# USB3.net
KiCad netlist of a schematic drawn in Altium Designer
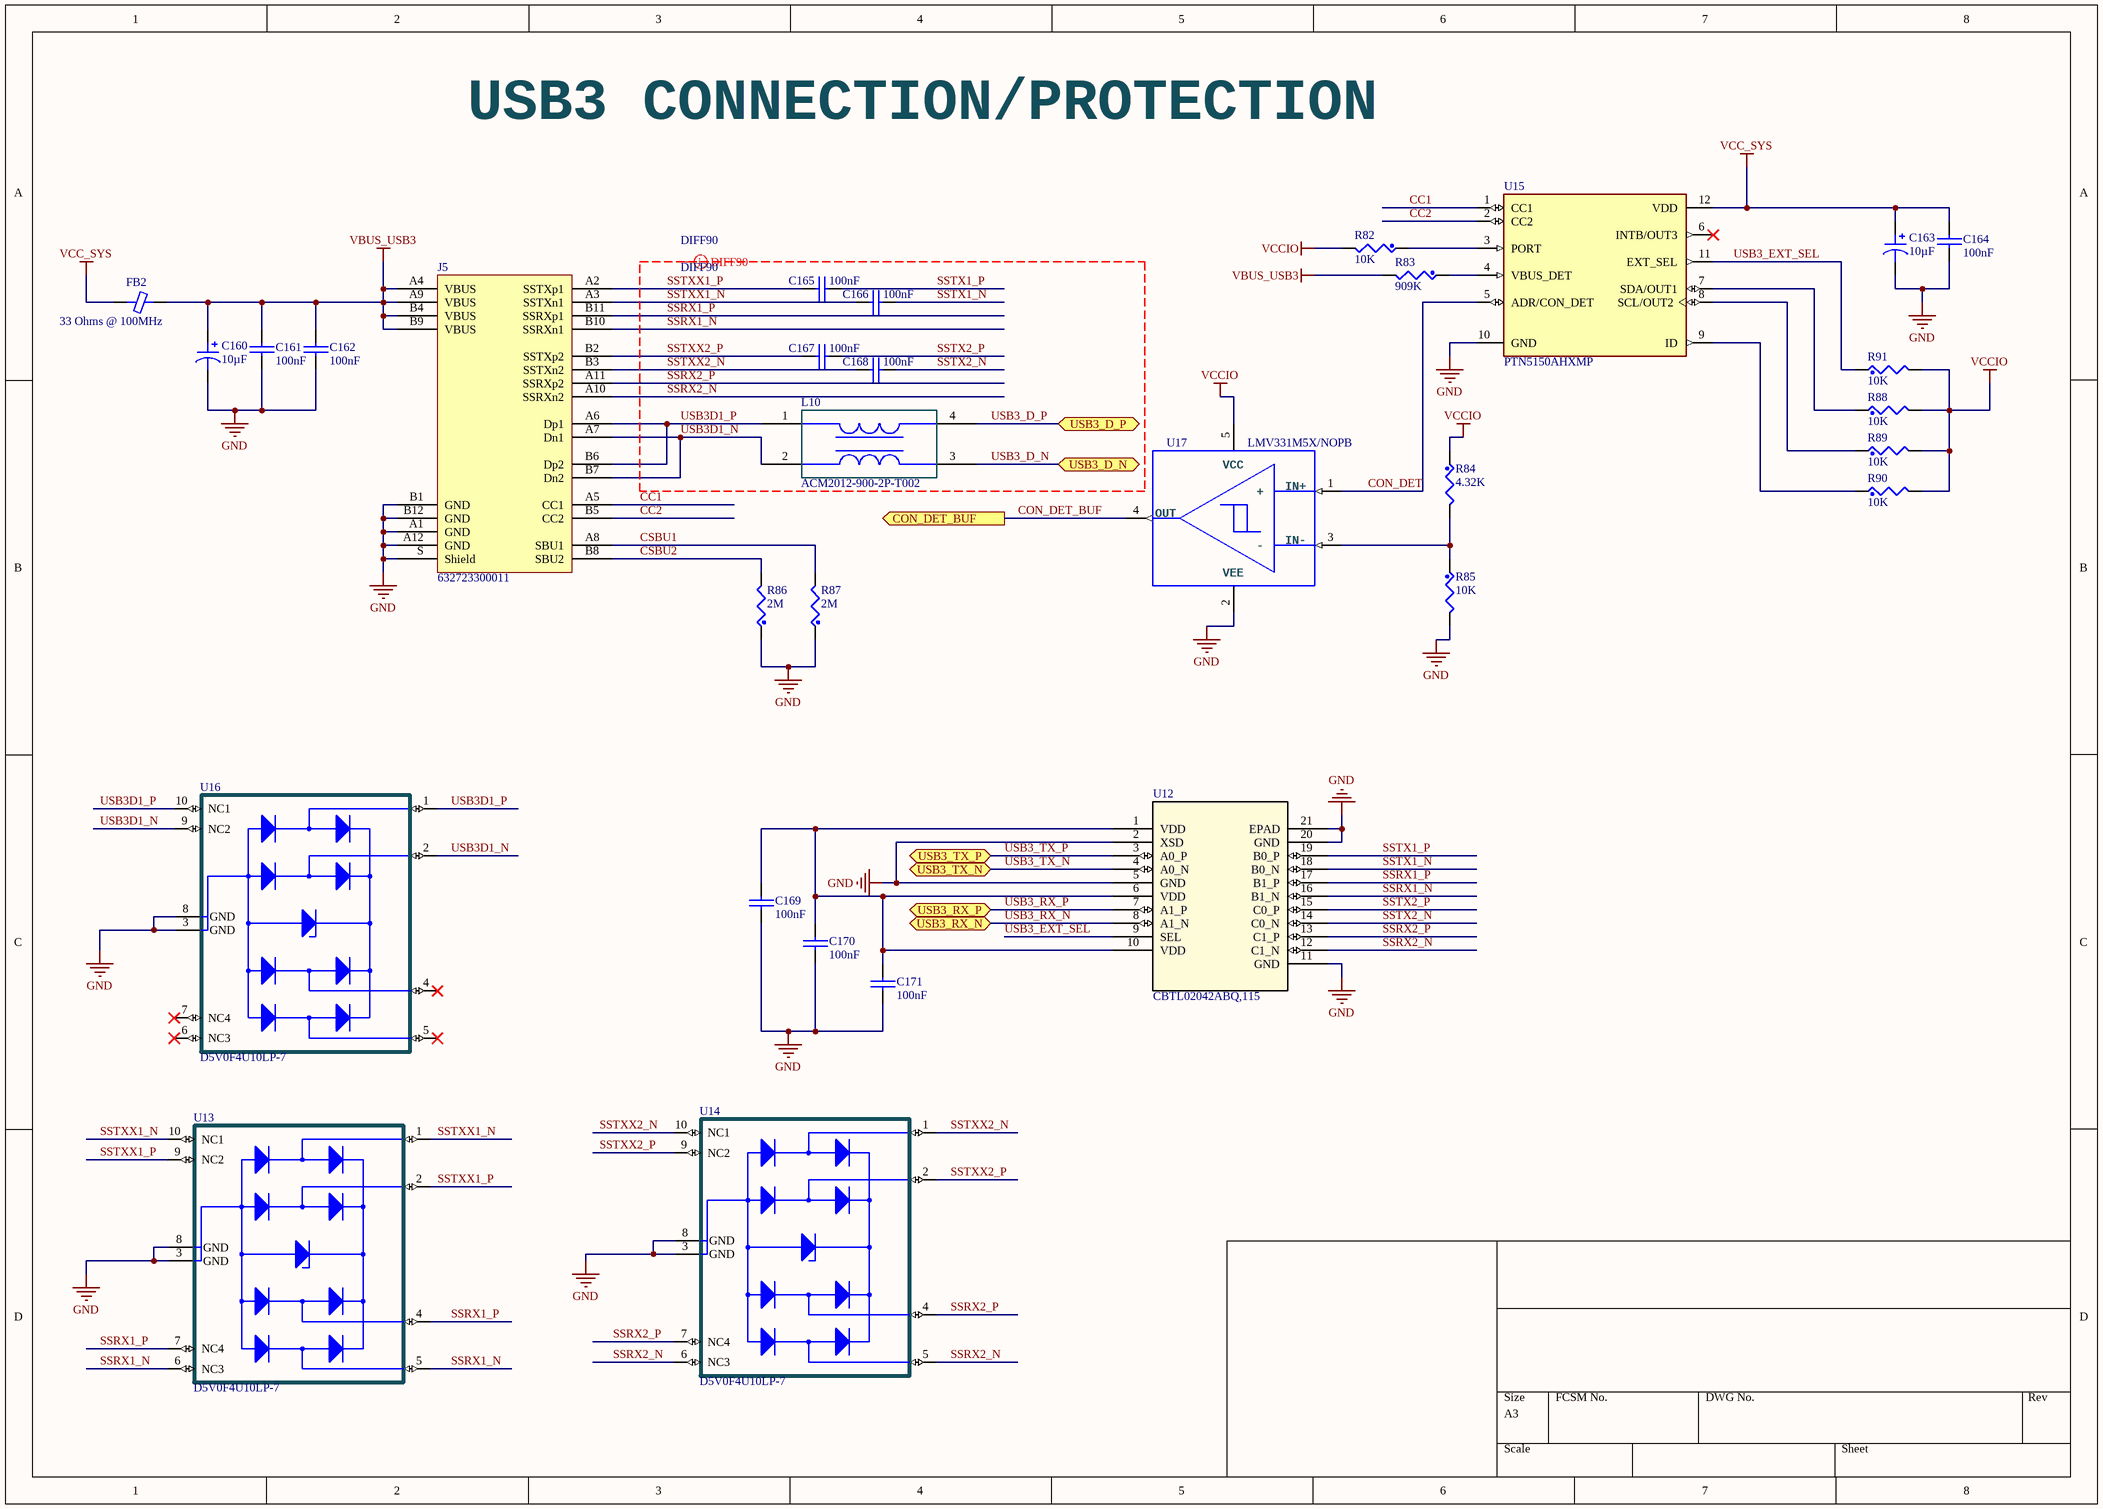
[diagram p0: USB3.SchDoc]

(export (version "E")
  (design (tool "Eeschema 10.0.6"))
  (components
    (comp (ref "C160")
      (value "10µF")
      (footprint "CAP POL 1206_3216")
      (description "CAP TANT 10UF 20% 10V 1206")
      (fields (field (name "PART NUMBER") "ATCC-211A-010-106M-T") (field (name "MANUFACTURER") "Abracon LLC"))
      (libsource (lib "Celestial Altium Library - altium_library") (part "Polarised Capacitor"))
    )
    (comp (ref "C161")
      (value "100nF")
      (footprint "0402_CC - C")
      (libsource (lib "AAR_RockChip_RK3328") (part "CAP_NP"))
    )
    (comp (ref "C162")
      (value "100nF")
      (footprint "0402_CC - C")
      (libsource (lib "AAR_RockChip_RK3328") (part "CAP_NP"))
    )
    (comp (ref "C163")
      (value "10µF")
      (footprint "CAP POL 1206_3216")
      (description "CAP TANT 10UF 20% 10V 1206")
      (fields (field (name "PART NUMBER") "ATCC-211A-010-106M-T") (field (name "MANUFACTURER") "Abracon LLC"))
      (libsource (lib "Celestial Altium Library - altium_library") (part "Polarised Capacitor"))
    )
    (comp (ref "C164")
      (value "100nF")
      (footprint "0402_CC - C")
      (libsource (lib "AAR_RockChip_RK3328") (part "CAP_NP"))
    )
    (comp (ref "C165")
      (value "100nF")
      (footprint "0402_CC - C")
      (libsource (lib "AAR_RockChip_RK3328") (part "CAP_NP"))
    )
    (comp (ref "C166")
      (value "100nF")
      (footprint "0402_CC - C")
      (libsource (lib "AAR_RockChip_RK3328") (part "CAP_NP"))
    )
    (comp (ref "C167")
      (value "100nF")
      (footprint "0402_CC - C")
      (libsource (lib "AAR_RockChip_RK3328") (part "CAP_NP"))
    )
    (comp (ref "C168")
      (value "100nF")
      (footprint "0402_CC - C")
      (libsource (lib "AAR_RockChip_RK3328") (part "CAP_NP"))
    )
    (comp (ref "C169")
      (value "100nF")
      (footprint "0402_CC - C")
      (libsource (lib "AAR_RockChip_RK3328") (part "CAP_NP"))
    )
    (comp (ref "C170")
      (value "100nF")
      (footprint "0402_CC - C")
      (libsource (lib "AAR_RockChip_RK3328") (part "CAP_NP"))
    )
    (comp (ref "C171")
      (value "100nF")
      (footprint "0402_CC - C")
      (libsource (lib "AAR_RockChip_RK3328") (part "CAP_NP"))
    )
    (comp (ref "FB2")
      (value "33 Ohms @ 100MHz")
      (footprint "FER 0805_2012")
      (description "FERRITE BEAD 33 OHM 0805 1LN")
      (fields (field (name "PART NUMBER") "Z0805C330ASMST") (field (name "MANUFACTURER") "KEMET"))
      (libsource (lib "Celestial Altium Library - altium_library") (part "Ferrite Chip"))
    )
    (comp (ref "J5")
      (value "632723300011")
      (footprint "WURTH 632723300011")
      (description "CONN RCP USB3.1 TYPEC 24P SMD RA")
      (fields (field (name "MANUFACTURER") "Würth Elektronik"))
      (libsource (lib "Celestial Altium Library - altium_library") (part "USB 3.0 Type C"))
    )
    (comp (ref "L10")
      (value "ACM2012-900-2P-T002")
      (footprint "FP-ACM2012-MFG")
      (description "CMC 400MA 2LN 90 OHM SMD")
      (fields (field (name "COPYRIGHT") "Copyright (C) 2022 Ultra Librarian. All rights reserved."))
      (libsource (lib "AAR_RockChip_RK3328") (part "ACM2012-900-2P-T002"))
    )
    (comp (ref "R82")
      (value "10K")
      (footprint "0402_CR")
      (libsource (lib "AAR_RockChip_RK3328") (part "RES"))
    )
    (comp (ref "R83")
      (value "909K")
      (footprint "0402_CR")
      (libsource (lib "AAR_RockChip_RK3328") (part "RES"))
    )
    (comp (ref "R84")
      (value "4.32K")
      (footprint "0402_CR")
      (libsource (lib "AAR_RockChip_RK3328") (part "RES"))
    )
    (comp (ref "R85")
      (value "10K")
      (footprint "0402_CR")
      (libsource (lib "AAR_RockChip_RK3328") (part "RES"))
    )
    (comp (ref "R86") (value "2M") (footprint "0402_CR") (libsource (lib "AAR_RockChip_RK3328") (part "RES")))
    (comp (ref "R87") (value "2M") (footprint "0402_CR") (libsource (lib "AAR_RockChip_RK3328") (part "RES")))
    (comp (ref "R88")
      (value "10K")
      (footprint "0402_CR")
      (libsource (lib "AAR_RockChip_RK3328") (part "RES"))
    )
    (comp (ref "R89")
      (value "10K")
      (footprint "0402_CR")
      (libsource (lib "AAR_RockChip_RK3328") (part "RES"))
    )
    (comp (ref "R90")
      (value "10K")
      (footprint "0402_CR")
      (libsource (lib "AAR_RockChip_RK3328") (part "RES"))
    )
    (comp (ref "R91")
      (value "10K")
      (footprint "0402_CR")
      (libsource (lib "AAR_RockChip_RK3328") (part "RES"))
    )
    (comp (ref "U12")
      (value "CBTL02042ABQ,115")
      (footprint "DHVQFN20_SOT764-1_NXP-L")
      (description "IC MUX/DEMUX 2:1 PCI 20DHVQFN")
      (fields (field (name "COPYRIGHT") "Copyright (C) 2022 Ultra Librarian. All rights reserved."))
      (libsource (lib "AAR_RockChip_RK3328") (part "CBTL02042ABQ,115"))
    )
    (comp (ref "U13")
      (value "D5V0F4U10LP-7")
      (footprint "TI_TPD4E05U06DQAR")
      (description "TVS DIODE 5.5VWM 12VC U-DFN2510")
      (fields (field (name "MFR") "Diodes Incorporated") (field (name "CREATOR") "AAR"))
      (libsource (lib "AAR_RockChip_RK3328") (part "D5V0F4U10LP-7"))
    )
    (comp (ref "U14")
      (value "D5V0F4U10LP-7")
      (footprint "TI_TPD4E05U06DQAR")
      (description "TVS DIODE 5.5VWM 12VC U-DFN2510")
      (fields (field (name "MFR") "Diodes Incorporated") (field (name "CREATOR") "AAR"))
      (libsource (lib "AAR_RockChip_RK3328") (part "D5V0F4U10LP-7"))
    )
    (comp (ref "U15")
      (value "PTN5150AHXMP")
      (footprint "USBCONTROLLER_PTN5150AHXMP")
      (description "USB Controller USB Interface 12-X2QFN (1.6x1.6)")
      (fields (field (name "MFR") "NXP USA"))
      (libsource (lib "AAR_RockChip_RK3328") (part "PTN5150AHXMP"))
    )
    (comp (ref "U16")
      (value "D5V0F4U10LP-7")
      (footprint "TI_TPD4E05U06DQAR")
      (description "TVS DIODE 5.5VWM 12VC U-DFN2510")
      (fields (field (name "MFR") "Diodes Incorporated") (field (name "CREATOR") "AAR"))
      (libsource (lib "AAR_RockChip_RK3328") (part "D5V0F4U10LP-7"))
    )
    (comp (ref "U17")
      (value "LMV331M5X/NOPB")
      (footprint "MF05A")
      (description "IC COMPARATOR TINY LV SOT23-5")
      (fields
        (field (name "PARTNUMBER") "LMV331M5")
        (field (name "MANUFACTURER") "NationalSemiconductor")
        (field (name "COPYRIGHT") "Copyright (C) 2022 Ultra Librarian. All rights reserved.")
        (field (name "PUBLISHER") "NationalSemiconductor")
      )
      (libsource (lib "AAR_RockChip_RK3328") (part "LMV331M5X/NOPB"))
    )
  )
  (nets
    (net (code "1") (name "/CC1") (class "Default")
      (node (ref "J5") (pin "A5") (pinfunction "CC1_A5") (pintype "passive"))
      (node (ref "U15") (pin "1") (pinfunction "CC1_1") (pintype "bidirectional"))
    )
    (net (code "2") (name "/CC2") (class "Default")
      (node (ref "J5") (pin "B5") (pinfunction "CC2_B5") (pintype "passive"))
      (node (ref "U15") (pin "2") (pinfunction "CC2_2") (pintype "bidirectional"))
    )
    (net (code "3") (name "/CON_DET") (class "Default")
      (node (ref "U15") (pin "5") (pinfunction "ADR/CON_DET_5") (pintype "bidirectional"))
      (node (ref "U17") (pin "1") (pinfunction "IN+_1") (pintype "input"))
    )
    (net (code "4") (name "/CON_DET_BUF") (class "Default")
      (node (ref "U17") (pin "4") (pinfunction "OUT_4") (pintype "output"))
    )
    (net (code "5") (name "/CSBU1") (class "Default")
      (node (ref "J5") (pin "A8") (pinfunction "SBU1_A8") (pintype "passive"))
      (node (ref "R87") (pin "2") (pinfunction "2_2") (pintype "passive"))
    )
    (net (code "6") (name "/CSBU2") (class "Default")
      (node (ref "J5") (pin "B8") (pinfunction "SBU2_B8") (pintype "passive"))
      (node (ref "R86") (pin "2") (pinfunction "2_2") (pintype "passive"))
    )
    (net (code "7") (name "/SSRX1_N") (class "Default")
      (node (ref "J5") (pin "B10") (pinfunction "SSRXn1_B10") (pintype "passive"))
      (node (ref "U12") (pin "16") (pinfunction "B1_N_16") (pintype "bidirectional"))
      (node (ref "U13") (pin "5") (pinfunction "D2-_5") (pintype "bidirectional"))
      (node (ref "U13") (pin "6") (pinfunction "NC3_6") (pintype "bidirectional"))
    )
    (net (code "8") (name "/SSRX1_P") (class "Default")
      (node (ref "J5") (pin "B11") (pinfunction "SSRXp1_B11") (pintype "passive"))
      (node (ref "U12") (pin "17") (pinfunction "B1_P_17") (pintype "bidirectional"))
      (node (ref "U13") (pin "4") (pinfunction "D2+_4") (pintype "bidirectional"))
      (node (ref "U13") (pin "7") (pinfunction "NC4_7") (pintype "bidirectional"))
    )
    (net (code "9") (name "/SSRX2_N") (class "Default")
      (node (ref "J5") (pin "A10") (pinfunction "SSRXn2_A10") (pintype "passive"))
      (node (ref "U12") (pin "12") (pinfunction "C1_N_12") (pintype "bidirectional"))
      (node (ref "U14") (pin "5") (pinfunction "D2-_5") (pintype "bidirectional"))
      (node (ref "U14") (pin "6") (pinfunction "NC3_6") (pintype "bidirectional"))
    )
    (net (code "10") (name "/SSRX2_P") (class "Default")
      (node (ref "J5") (pin "A11") (pinfunction "SSRXp2_A11") (pintype "passive"))
      (node (ref "U12") (pin "13") (pinfunction "C1_P_13") (pintype "bidirectional"))
      (node (ref "U14") (pin "4") (pinfunction "D2+_4") (pintype "bidirectional"))
      (node (ref "U14") (pin "7") (pinfunction "NC4_7") (pintype "bidirectional"))
    )
    (net (code "11") (name "/SSTX1_N") (class "Default")
      (node (ref "C166") (pin "2") (pinfunction "2_2") (pintype "passive"))
      (node (ref "U12") (pin "18") (pinfunction "B0_N_18") (pintype "bidirectional"))
    )
    (net (code "12") (name "/SSTX1_P") (class "Default")
      (node (ref "C165") (pin "2") (pinfunction "2_2") (pintype "passive"))
      (node (ref "U12") (pin "19") (pinfunction "B0_P_19") (pintype "bidirectional"))
    )
    (net (code "13") (name "/SSTX2_N") (class "Default")
      (node (ref "C168") (pin "2") (pinfunction "2_2") (pintype "passive"))
      (node (ref "U12") (pin "14") (pinfunction "C0_N_14") (pintype "bidirectional"))
    )
    (net (code "14") (name "/SSTX2_P") (class "Default")
      (node (ref "C167") (pin "2") (pinfunction "2_2") (pintype "passive"))
      (node (ref "U12") (pin "15") (pinfunction "C0_P_15") (pintype "bidirectional"))
    )
    (net (code "15") (name "/SSTXX1_N") (class "Default")
      (node (ref "C166") (pin "1") (pinfunction "1_1") (pintype "passive"))
      (node (ref "J5") (pin "A3") (pinfunction "SSTXn1_A3") (pintype "passive"))
      (node (ref "U13") (pin "1") (pinfunction "D1+_1") (pintype "bidirectional"))
      (node (ref "U13") (pin "10") (pinfunction "NC1_10") (pintype "bidirectional"))
    )
    (net (code "16") (name "/SSTXX1_P") (class "Default")
      (node (ref "C165") (pin "1") (pinfunction "1_1") (pintype "passive"))
      (node (ref "J5") (pin "A2") (pinfunction "SSTXp1_A2") (pintype "passive"))
      (node (ref "U13") (pin "2") (pinfunction "D1-_2") (pintype "bidirectional"))
      (node (ref "U13") (pin "9") (pinfunction "NC2_9") (pintype "bidirectional"))
    )
    (net (code "17") (name "/SSTXX2_N") (class "Default")
      (node (ref "C168") (pin "1") (pinfunction "1_1") (pintype "passive"))
      (node (ref "J5") (pin "B3") (pinfunction "SSTXn2_B3") (pintype "passive"))
      (node (ref "U14") (pin "1") (pinfunction "D1+_1") (pintype "bidirectional"))
      (node (ref "U14") (pin "10") (pinfunction "NC1_10") (pintype "bidirectional"))
    )
    (net (code "18") (name "/SSTXX2_P") (class "Default")
      (node (ref "C167") (pin "1") (pinfunction "1_1") (pintype "passive"))
      (node (ref "J5") (pin "B2") (pinfunction "SSTXp2_B2") (pintype "passive"))
      (node (ref "U14") (pin "2") (pinfunction "D1-_2") (pintype "bidirectional"))
      (node (ref "U14") (pin "9") (pinfunction "NC2_9") (pintype "bidirectional"))
    )
    (net (code "19") (name "/USB3D1_N") (class "Default")
      (node (ref "J5") (pin "A7") (pinfunction "Dn1_A7") (pintype "passive"))
      (node (ref "J5") (pin "B7") (pinfunction "Dn2_B7") (pintype "passive"))
      (node (ref "L10") (pin "2") (pinfunction "2_2") (pintype "passive"))
      (node (ref "U16") (pin "2") (pinfunction "D1-_2") (pintype "bidirectional"))
      (node (ref "U16") (pin "9") (pinfunction "NC2_9") (pintype "bidirectional"))
    )
    (net (code "20") (name "/USB3D1_P") (class "Default")
      (node (ref "J5") (pin "A6") (pinfunction "Dp1_A6") (pintype "passive"))
      (node (ref "J5") (pin "B6") (pinfunction "Dp2_B6") (pintype "passive"))
      (node (ref "L10") (pin "1") (pinfunction "1_1") (pintype "passive"))
      (node (ref "U16") (pin "1") (pinfunction "D1+_1") (pintype "bidirectional"))
      (node (ref "U16") (pin "10") (pinfunction "NC1_10") (pintype "bidirectional"))
    )
    (net (code "21") (name "/USB3_D_N") (class "Default")
      (node (ref "L10") (pin "3") (pinfunction "3_3") (pintype "passive"))
    )
    (net (code "22") (name "/USB3_D_P") (class "Default")
      (node (ref "L10") (pin "4") (pinfunction "4_4") (pintype "passive"))
    )
    (net (code "23") (name "/USB3_EXT_SEL") (class "Default")
      (node (ref "R91") (pin "1") (pinfunction "1_1") (pintype "passive"))
      (node (ref "U12") (pin "9") (pinfunction "SEL_9") (pintype "passive"))
      (node (ref "U15") (pin "11") (pinfunction "EXT_SEL_11") (pintype "output"))
    )
    (net (code "24") (name "/USB3_RX_N") (class "Default")
      (node (ref "U12") (pin "8") (pinfunction "A1_N_8") (pintype "bidirectional"))
    )
    (net (code "25") (name "/USB3_RX_P") (class "Default")
      (node (ref "U12") (pin "7") (pinfunction "A1_P_7") (pintype "bidirectional"))
    )
    (net (code "26") (name "/USB3_TX_N") (class "Default")
      (node (ref "U12") (pin "4") (pinfunction "A0_N_4") (pintype "bidirectional"))
    )
    (net (code "27") (name "/USB3_TX_P") (class "Default")
      (node (ref "U12") (pin "3") (pinfunction "A0_P_3") (pintype "bidirectional"))
    )
    (net (code "28") (name "GND") (class "Default")
      (node (ref "C160") (pin "2") (pinfunction "2_2") (pintype "passive"))
      (node (ref "C161") (pin "2") (pinfunction "2_2") (pintype "passive"))
      (node (ref "C162") (pin "2") (pinfunction "2_2") (pintype "passive"))
      (node (ref "C163") (pin "2") (pinfunction "2_2") (pintype "passive"))
      (node (ref "C164") (pin "2") (pinfunction "2_2") (pintype "passive"))
      (node (ref "C169") (pin "2") (pinfunction "2_2") (pintype "passive"))
      (node (ref "C170") (pin "2") (pinfunction "2_2") (pintype "passive"))
      (node (ref "C171") (pin "2") (pinfunction "2_2") (pintype "passive"))
      (node (ref "J5") (pin "A1") (pinfunction "GND_A1") (pintype "passive"))
      (node (ref "J5") (pin "A12") (pinfunction "GND_A12") (pintype "passive"))
      (node (ref "J5") (pin "B1") (pinfunction "GND_B1") (pintype "passive"))
      (node (ref "J5") (pin "B12") (pinfunction "GND_B12") (pintype "passive"))
      (node (ref "J5") (pin "S") (pinfunction "Shield_S") (pintype "passive"))
      (node (ref "R85") (pin "2") (pinfunction "2_2") (pintype "passive"))
      (node (ref "R86") (pin "1") (pinfunction "1_1") (pintype "passive"))
      (node (ref "R87") (pin "1") (pinfunction "1_1") (pintype "passive"))
      (node (ref "U12") (pin "11") (pinfunction "GND_11") (pintype "passive"))
      (node (ref "U12") (pin "2") (pinfunction "XSD_2") (pintype "passive"))
      (node (ref "U12") (pin "20") (pinfunction "GND_20") (pintype "passive"))
      (node (ref "U12") (pin "21") (pinfunction "EPAD_21") (pintype "passive"))
      (node (ref "U12") (pin "5") (pinfunction "GND_5") (pintype "passive"))
      (node (ref "U13") (pin "3") (pinfunction "GND_3") (pintype "power_in"))
      (node (ref "U13") (pin "8") (pinfunction "GND_8") (pintype "power_in"))
      (node (ref "U14") (pin "3") (pinfunction "GND_3") (pintype "power_in"))
      (node (ref "U14") (pin "8") (pinfunction "GND_8") (pintype "power_in"))
      (node (ref "U15") (pin "10") (pinfunction "GND_10") (pintype "power_in"))
      (node (ref "U16") (pin "3") (pinfunction "GND_3") (pintype "power_in"))
      (node (ref "U16") (pin "8") (pinfunction "GND_8") (pintype "power_in"))
      (node (ref "U17") (pin "2") (pinfunction "V-_2") (pintype "power_in"))
    )
    (net (code "29") (name "Net-(C169-Pad1)") (class "Default")
      (node (ref "C169") (pin "1") (pinfunction "1_1") (pintype "passive"))
      (node (ref "C170") (pin "1") (pinfunction "1_1") (pintype "passive"))
      (node (ref "C171") (pin "1") (pinfunction "1_1") (pintype "passive"))
      (node (ref "U12") (pin "1") (pinfunction "VDD_1") (pintype "passive"))
      (node (ref "U12") (pin "10") (pinfunction "VDD_10") (pintype "power_in"))
      (node (ref "U12") (pin "6") (pinfunction "VDD_6") (pintype "power_in"))
    )
    (net (code "30") (name "Net-(U15-ID)") (class "Default")
      (node (ref "R90") (pin "1") (pinfunction "1_1") (pintype "passive"))
      (node (ref "U15") (pin "9") (pinfunction "ID_9") (pintype "output"))
    )
    (net (code "31") (name "Net-(U15-PORT)") (class "Default")
      (node (ref "R82") (pin "1") (pinfunction "1_1") (pintype "passive"))
      (node (ref "U15") (pin "3") (pinfunction "PORT_3") (pintype "input"))
    )
    (net (code "32") (name "Net-(U15-SCL{slash}OUT2)") (class "Default")
      (node (ref "R89") (pin "1") (pinfunction "1_1") (pintype "passive"))
      (node (ref "U15") (pin "8") (pinfunction "SCL/OUT2_8") (pintype "bidirectional"))
    )
    (net (code "33") (name "Net-(U15-SDA{slash}OUT1)") (class "Default")
      (node (ref "R88") (pin "1") (pinfunction "1_1") (pintype "passive"))
      (node (ref "U15") (pin "7") (pinfunction "SDA/OUT1_7") (pintype "bidirectional"))
    )
    (net (code "34") (name "Net-(U15-VBUS_DET)") (class "Default")
      (node (ref "R83") (pin "1") (pinfunction "1_1") (pintype "passive"))
      (node (ref "U15") (pin "4") (pinfunction "VBUS_DET_4") (pintype "input"))
    )
    (net (code "35") (name "Net-(U17-IN-)") (class "Default")
      (node (ref "R84") (pin "2") (pinfunction "2_2") (pintype "passive"))
      (node (ref "R85") (pin "1") (pinfunction "1_1") (pintype "passive"))
      (node (ref "U17") (pin "3") (pinfunction "IN-_3") (pintype "input"))
    )
    (net (code "36") (name "VBUS_USB3") (class "Default")
      (node (ref "C160") (pin "1") (pinfunction "1_1") (pintype "passive"))
      (node (ref "C161") (pin "1") (pinfunction "1_1") (pintype "passive"))
      (node (ref "C162") (pin "1") (pinfunction "1_1") (pintype "passive"))
      (node (ref "FB2") (pin "2") (pinfunction "2_2") (pintype "passive"))
      (node (ref "J5") (pin "A4") (pinfunction "VBUS_A4") (pintype "passive"))
      (node (ref "J5") (pin "A9") (pinfunction "VBUS_A9") (pintype "passive"))
      (node (ref "J5") (pin "B4") (pinfunction "VBUS_B4") (pintype "passive"))
      (node (ref "J5") (pin "B9") (pinfunction "VBUS_B9") (pintype "passive"))
      (node (ref "R83") (pin "2") (pinfunction "2_2") (pintype "passive"))
    )
    (net (code "37") (name "VCCIO") (class "Default")
      (node (ref "R82") (pin "2") (pinfunction "2_2") (pintype "passive"))
      (node (ref "R84") (pin "1") (pinfunction "1_1") (pintype "passive"))
      (node (ref "R88") (pin "2") (pinfunction "2_2") (pintype "passive"))
      (node (ref "R89") (pin "2") (pinfunction "2_2") (pintype "passive"))
      (node (ref "R90") (pin "2") (pinfunction "2_2") (pintype "passive"))
      (node (ref "R91") (pin "2") (pinfunction "2_2") (pintype "passive"))
      (node (ref "U17") (pin "5") (pinfunction "V+_5") (pintype "power_in"))
    )
    (net (code "38") (name "VCC_SYS") (class "Default")
      (node (ref "C163") (pin "1") (pinfunction "1_1") (pintype "passive"))
      (node (ref "C164") (pin "1") (pinfunction "1_1") (pintype "passive"))
      (node (ref "FB2") (pin "1") (pinfunction "1_1") (pintype "passive"))
      (node (ref "U15") (pin "12") (pinfunction "VDD_12") (pintype "power_in"))
    )
    (net (code "39") (name "unconnected-(U15-INTB{slash}OUT3-Pad6)") (class "Default")
      (node (ref "U15") (pin "6") (pinfunction "INTB/OUT3_6") (pintype "output+no_connect"))
    )
    (net (code "40") (name "unconnected-(U16-D2+-Pad4)") (class "Default")
      (node (ref "U16") (pin "4") (pinfunction "D2+_4") (pintype "bidirectional+no_connect"))
    )
    (net (code "41") (name "unconnected-(U16-D2--Pad5)") (class "Default")
      (node (ref "U16") (pin "5") (pinfunction "D2-_5") (pintype "bidirectional+no_connect"))
    )
    (net (code "42") (name "unconnected-(U16-NC3-Pad6)") (class "Default")
      (node (ref "U16") (pin "6") (pinfunction "NC3_6") (pintype "bidirectional+no_connect"))
    )
    (net (code "43") (name "unconnected-(U16-NC4-Pad7)") (class "Default")
      (node (ref "U16") (pin "7") (pinfunction "NC4_7") (pintype "bidirectional+no_connect"))
    )
  )
)
